# TDA1308.net
KiCad netlist of a schematic drawn in Altium Designer
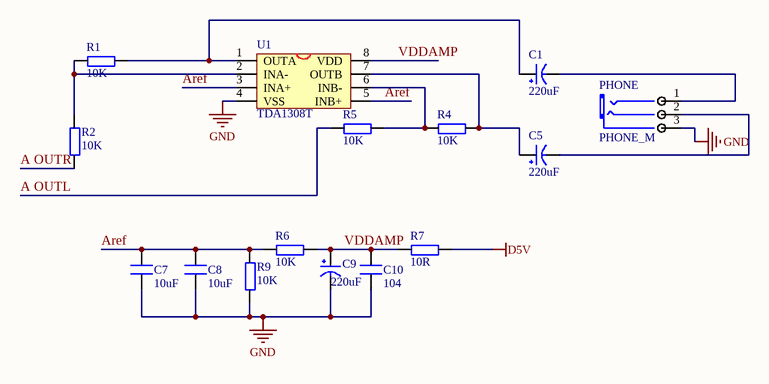
[diagram p0: TDA1308.SchDoc]

(export (version "E")
  (design (tool "Eeschema 10.0.6"))
  (components
    (comp (ref "C1") (value "220uF") (footprint "CC6.56.5") (libsource (lib "战舰STM32开发板底板封装库") (part "CAP")))
    (comp (ref "C5") (value "220uF") (footprint "CC6.56.5") (libsource (lib "战舰STM32开发板底板封装库") (part "CAP")))
    (comp (ref "C7") (value "10uF") (footprint "0603P") (libsource (lib "战舰STM32开发板底板封装库") (part "C")))
    (comp (ref "C8") (value "10uF") (footprint "0603P") (libsource (lib "战舰STM32开发板底板封装库") (part "C")))
    (comp (ref "C9") (value "220uF") (footprint "CC6.56.5") (libsource (lib "") (part "CAP_1")))
    (comp (ref "C10") (value "104") (footprint "0603P") (libsource (lib "战舰STM32开发板底板封装库") (part "C")))
    (comp (ref "PHONE")
      (value "PHONE_M")
      (footprint "PHONE_ST")
      (libsource (lib "战舰STM32开发板底板封装库") (part "PHONE_M"))
    )
    (comp (ref "R1") (value "10K") (footprint "0603P") (libsource (lib "战舰STM32开发板底板封装库") (part "R")))
    (comp (ref "R2") (value "10K") (footprint "0603P") (libsource (lib "战舰STM32开发板底板封装库") (part "R")))
    (comp (ref "R4") (value "10K") (footprint "0603P") (libsource (lib "战舰STM32开发板底板封装库") (part "R")))
    (comp (ref "R5") (value "10K") (footprint "0603P") (libsource (lib "战舰STM32开发板底板封装库") (part "R")))
    (comp (ref "R6") (value "10K") (footprint "0603P") (libsource (lib "战舰STM32开发板底板封装库") (part "R")))
    (comp (ref "R7") (value "10R") (footprint "0603P") (libsource (lib "战舰STM32开发板底板封装库") (part "R")))
    (comp (ref "R9") (value "10K") (footprint "0603P") (libsource (lib "战舰STM32开发板底板封装库") (part "R")))
    (comp (ref "U1")
      (value "TDA1308T")
      (footprint "SOP-8")
      (libsource (lib "战舰STM32开发板底板封装库") (part "TDA1308"))
    )
  )
  (nets
    (net (code "1") (name "/A OUTL") (class "Default") (node (ref "R5") (pin "1") (pintype "passive")))
    (net (code "2") (name "/A OUTR") (class "Default") (node (ref "R2") (pin "1") (pintype "passive")))
    (net (code "3") (name "/Aref") (class "Default")
      (node (ref "C7") (pin "2") (pintype "passive"))
      (node (ref "C8") (pin "2") (pintype "passive"))
      (node (ref "R6") (pin "1") (pintype "passive"))
      (node (ref "R9") (pin "2") (pintype "passive"))
      (node (ref "U1") (pin "3") (pinfunction "INA+_3") (pintype "passive"))
      (node (ref "U1") (pin "5") (pinfunction "INB+_5") (pintype "passive"))
    )
    (net (code "4") (name "/VDDAMP") (class "Default")
      (node (ref "C10") (pin "2") (pintype "passive"))
      (node (ref "C9") (pin "1") (pinfunction "VCC_1") (pintype "passive"))
      (node (ref "R6") (pin "2") (pintype "passive"))
      (node (ref "R7") (pin "1") (pintype "passive"))
      (node (ref "U1") (pin "8") (pinfunction "VDD_8") (pintype "passive"))
    )
    (net (code "5") (name "D5V") (class "Default") (node (ref "R7") (pin "2") (pintype "passive")))
    (net (code "6") (name "GND") (class "Default")
      (node (ref "C10") (pin "1") (pintype "passive"))
      (node (ref "C7") (pin "1") (pintype "passive"))
      (node (ref "C8") (pin "1") (pintype "passive"))
      (node (ref "C9") (pin "2") (pinfunction "GND_2") (pintype "passive"))
      (node (ref "PHONE") (pin "3") (pinfunction "COM_3") (pintype "passive"))
      (node (ref "R9") (pin "1") (pintype "passive"))
      (node (ref "U1") (pin "4") (pinfunction "VSS_4") (pintype "passive"))
    )
    (net (code "7") (name "Net-(C1-GND)") (class "Default")
      (node (ref "C1") (pin "2") (pinfunction "GND_2") (pintype "passive"))
      (node (ref "PHONE") (pin "1") (pinfunction "CHL_1") (pintype "passive"))
    )
    (net (code "8") (name "Net-(C1-VCC)") (class "Default")
      (node (ref "C1") (pin "1") (pinfunction "VCC_1") (pintype "passive"))
      (node (ref "R1") (pin "2") (pintype "passive"))
      (node (ref "U1") (pin "1") (pinfunction "OUTA_1") (pintype "passive"))
    )
    (net (code "9") (name "Net-(C5-GND)") (class "Default")
      (node (ref "C5") (pin "2") (pinfunction "GND_2") (pintype "passive"))
      (node (ref "PHONE") (pin "2") (pinfunction "CHR_2") (pintype "passive"))
    )
    (net (code "10") (name "Net-(C5-VCC)") (class "Default")
      (node (ref "C5") (pin "1") (pinfunction "VCC_1") (pintype "passive"))
      (node (ref "R4") (pin "2") (pintype "passive"))
      (node (ref "U1") (pin "7") (pinfunction "OUTB_7") (pintype "passive"))
    )
    (net (code "11") (name "Net-(U1-INA-)") (class "Default")
      (node (ref "R1") (pin "1") (pintype "passive"))
      (node (ref "R2") (pin "2") (pintype "passive"))
      (node (ref "U1") (pin "2") (pinfunction "INA-_2") (pintype "passive"))
    )
    (net (code "12") (name "Net-(U1-INB-)") (class "Default")
      (node (ref "R4") (pin "1") (pintype "passive"))
      (node (ref "R5") (pin "2") (pintype "passive"))
      (node (ref "U1") (pin "6") (pinfunction "INB-_6") (pintype "passive"))
    )
  )
)
